# Connectors.net
KiCad netlist of a schematic drawn in Altium Designer
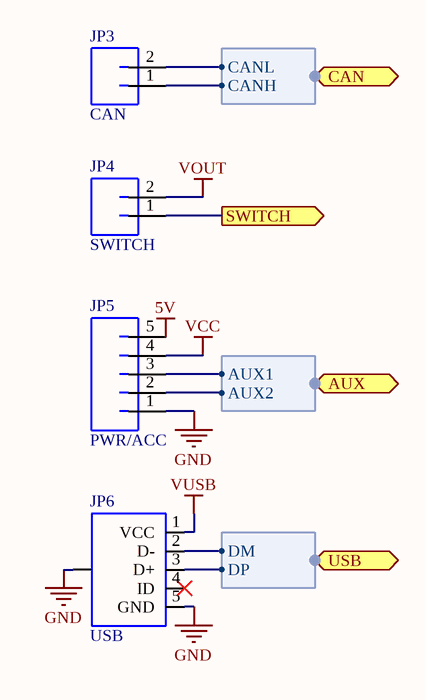
[diagram p0: Connectors.SchDoc]

(export (version "E")
  (design (tool "Eeschema 10.0.6"))
  (components
    (comp (ref "JP3")
      (value "CAN")
      (footprint "JST-PH-2-PTH-VERT")
      (fields
        (field (name "MANUFACTURER") "JST Sales America, Inc.")
        (field (name "PARTNUMBER") "B2B-PH-K-S(LF)(SN)")
      )
      (libsource (lib "Connectors") (part "JST_PH_2_VERT"))
    )
    (comp (ref "JP4")
      (value "SWITCH")
      (footprint "JST-PH-2-PTH-VERT")
      (fields
        (field (name "MANUFACTURER") "JST Sales America, Inc.")
        (field (name "PARTNUMBER") "B2B-PH-K-S(LF)(SN)")
      )
      (libsource (lib "Connectors") (part "JST_PH_2_VERT"))
    )
    (comp (ref "JP5")
      (value "PWR/ACC")
      (footprint "JST-PH-5-PTH-VERT")
      (fields
        (field (name "MANUFACTURER") "JST Sales America, Inc.")
        (field (name "PARTNUMBER") "B5B-PH-K-S(LF)(SN)")
      )
      (libsource (lib "Connectors") (part "JST_PH_5_VERT"))
    )
    (comp (ref "JP6")
      (value "USB")
      (footprint "USB-MICROB")
      (fields (field (name "PARTNUMBER") "10118192-0001LF") (field (name "MANUFACTURER") "Amphenol FCI"))
      (libsource (lib "Connectors") (part "USB_MICROB_SMT"))
    )
  )
  (nets
    (net (code "6") (name "/AUX1") (class "Default")
      (node (ref "JP5") (pin "3") (pinfunction "3_3") (pintype "passive"))
    )
    (net (code "7") (name "/AUX2") (class "Default")
      (node (ref "JP5") (pin "2") (pinfunction "2_2") (pintype "passive"))
    )
    (net (code "8") (name "/CANH") (class "Default")
      (node (ref "JP3") (pin "1") (pinfunction "1_1") (pintype "passive"))
    )
    (net (code "9") (name "/CANL") (class "Default")
      (node (ref "JP3") (pin "2") (pinfunction "2_2") (pintype "passive"))
    )
    (net (code "10") (name "/DM") (class "Default")
      (node (ref "JP6") (pin "2") (pinfunction "D-_2") (pintype "passive"))
    )
    (net (code "11") (name "/DP") (class "Default")
      (node (ref "JP6") (pin "3") (pinfunction "D+_3") (pintype "passive"))
    )
    (net (code "12") (name "/SWITCH") (class "Default")
      (node (ref "JP4") (pin "1") (pinfunction "1_1") (pintype "passive"))
    )
    (net (code "16") (name "5V") (class "Default")
      (node (ref "JP5") (pin "5") (pinfunction "5_5") (pintype "passive"))
    )
    (net (code "17") (name "GND") (class "Default")
      (node (ref "JP5") (pin "1") (pinfunction "1_1") (pintype "passive"))
      (node (ref "JP6") (pin "5") (pinfunction "GND_5") (pintype "passive"))
      (node (ref "JP6") (pin "6") (pinfunction "SHIELD_6") (pintype "passive"))
    )
    (net (code "18") (name "VCC") (class "Default")
      (node (ref "JP5") (pin "4") (pinfunction "4_4") (pintype "passive"))
    )
    (net (code "19") (name "VOUT") (class "Default")
      (node (ref "JP4") (pin "2") (pinfunction "2_2") (pintype "passive"))
    )
    (net (code "20") (name "VUSB") (class "Default")
      (node (ref "JP6") (pin "1") (pinfunction "VCC_1") (pintype "passive"))
    )
    (net (code "21") (name "unconnected-(JP6-ID-Pad4)") (class "Default")
      (node (ref "JP6") (pin "4") (pinfunction "ID_4") (pintype "passive+no_connect"))
    )
  )
)
